# RAUPS_SingleLayer_Stepper.net
KiCad netlist of a schematic drawn in EAGLE
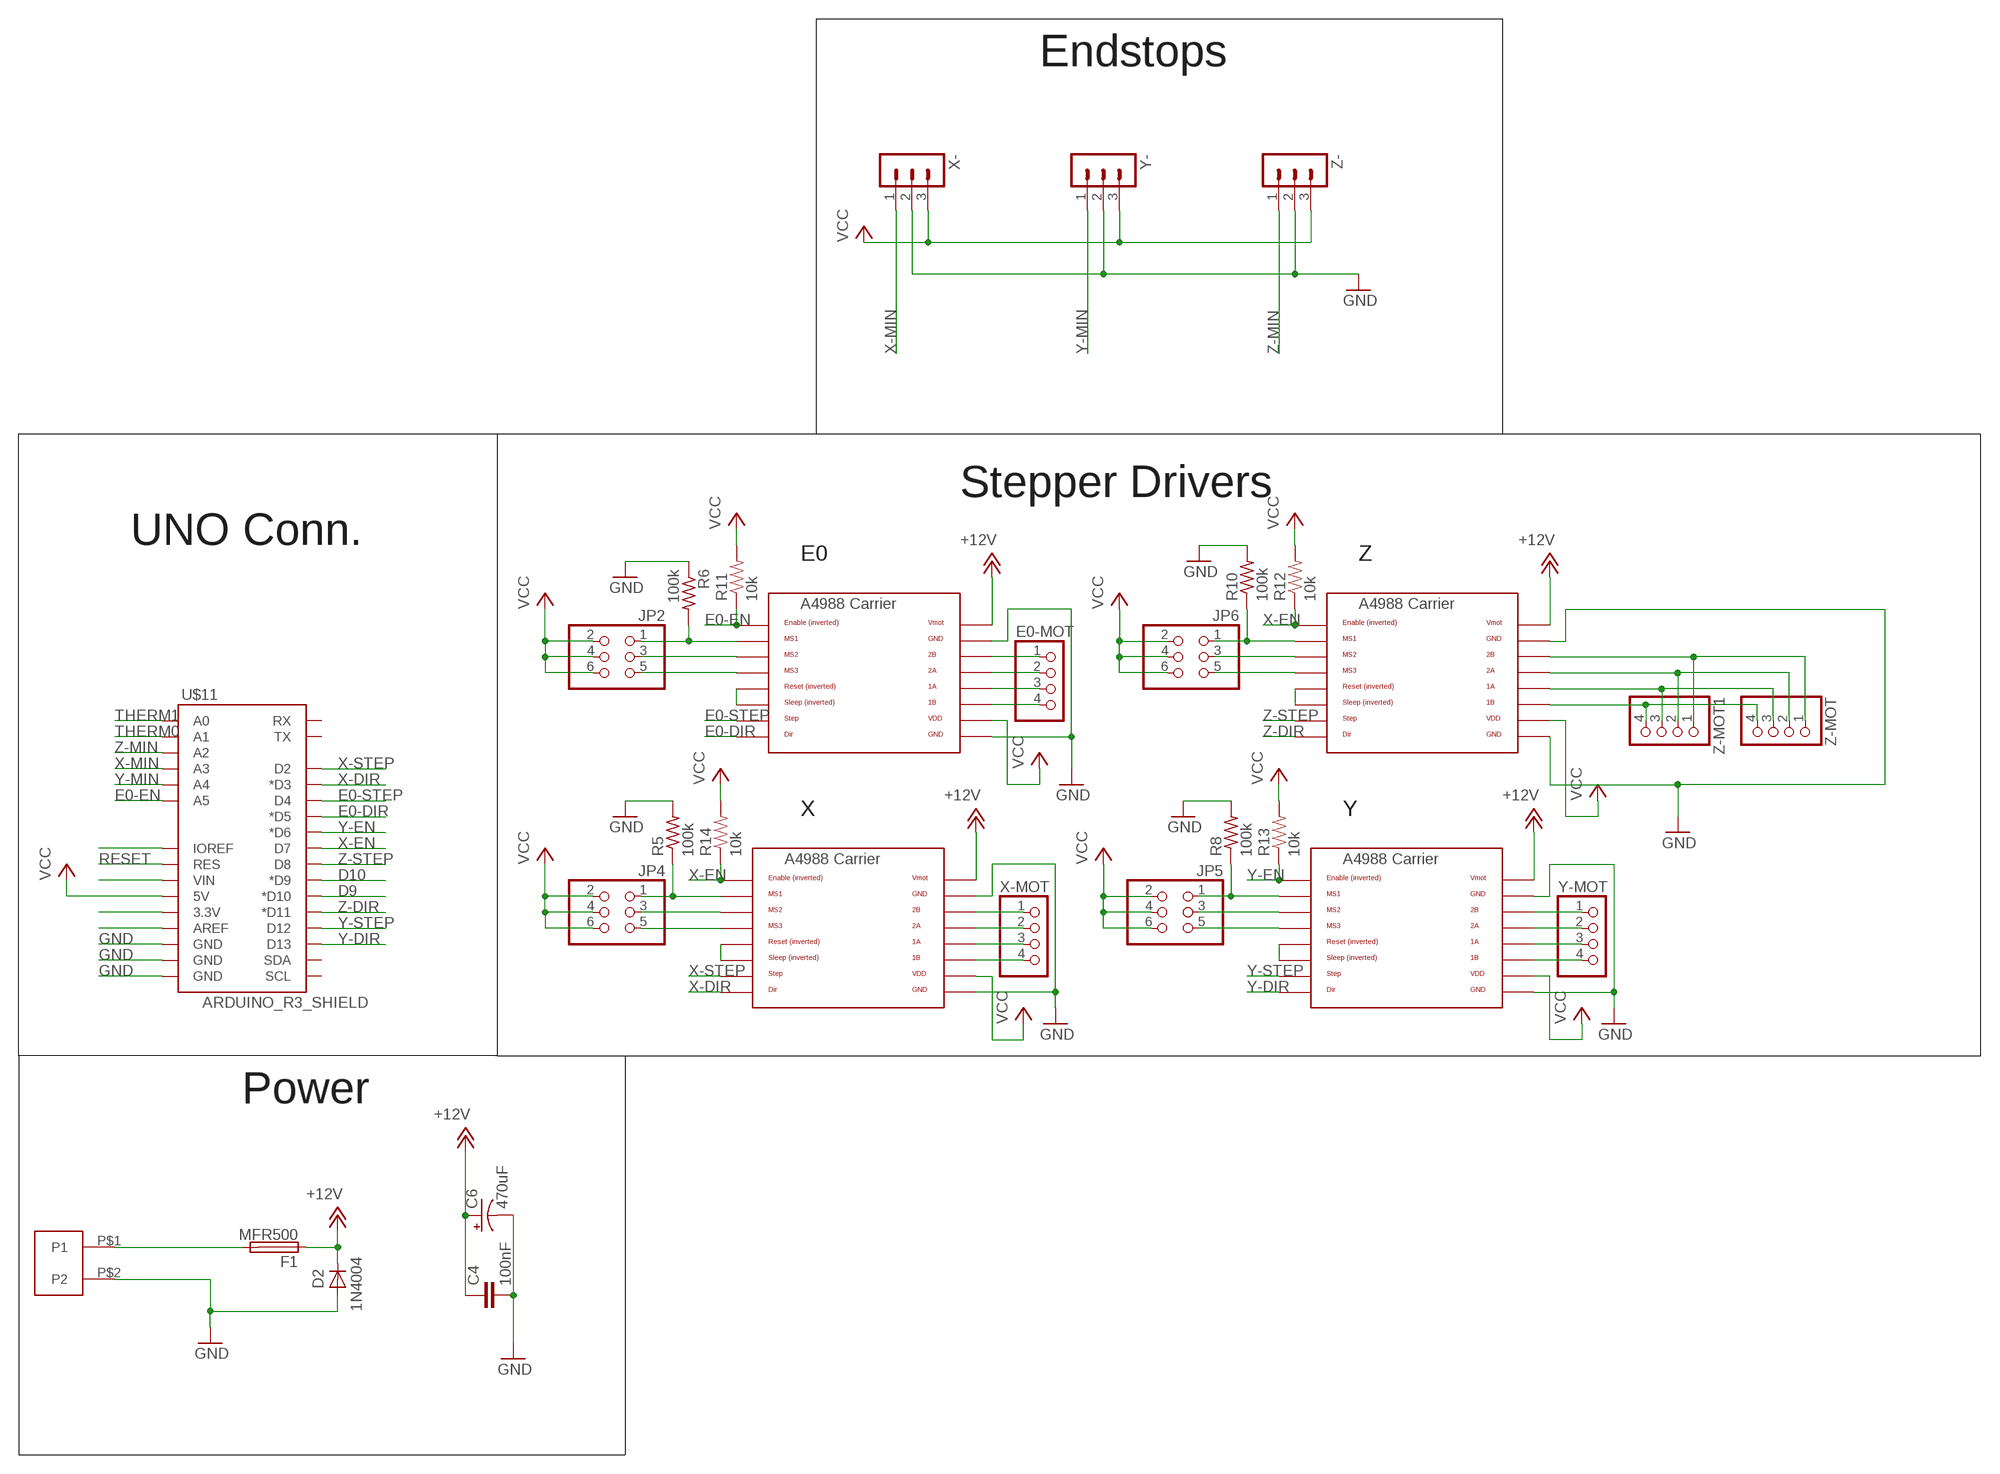
[diagram p0: schematic, sheet 1]

(export (version "E")
  (design (tool "Eeschema 10.0.6"))
  (components
    (comp (ref "C4")
      (value "100nF")
      (footprint "eagle-import:C2.5-3")
      (libsource (lib "eagle-import") (part "C2,5-3"))
    )
    (comp (ref "C6")
      (value "470uF")
      (footprint "eagle-import:E3,5-8")
      (libsource (lib "eagle-import") (part "CPOL-USE3.5-8"))
    )
    (comp (ref "D2")
      (value "1N4004")
      (footprint "eagle-import:DO41-10")
      (libsource (lib "eagle-import") (part "1N4004"))
    )
    (comp (ref "E0-MOT")
      (value "PINHD-1X4")
      (footprint "eagle-import:1X04")
      (libsource (lib "eagle-import") (part "PINHD-1X4"))
    )
    (comp (ref "F1")
      (value "MFR500")
      (footprint "eagle-import:MFR500")
      (libsource (lib "eagle-import") (part "PTCFUSE"))
    )
    (comp (ref "JP2")
      (value "PINHD-2X3")
      (footprint "eagle-import:2X03")
      (libsource (lib "eagle-import") (part "PINHD-2X3"))
    )
    (comp (ref "JP4")
      (value "PINHD-2X3")
      (footprint "eagle-import:2X03")
      (libsource (lib "eagle-import") (part "PINHD-2X3"))
    )
    (comp (ref "JP5")
      (value "PINHD-2X3")
      (footprint "eagle-import:2X03")
      (libsource (lib "eagle-import") (part "PINHD-2X3"))
    )
    (comp (ref "JP6")
      (value "PINHD-2X3")
      (footprint "eagle-import:2X03")
      (libsource (lib "eagle-import") (part "PINHD-2X3"))
    )
    (comp (ref "R5")
      (value "100k")
      (footprint "eagle-import:0207_7")
      (libsource (lib "eagle-import") (part "R-US_0207/7"))
    )
    (comp (ref "R6")
      (value "100k")
      (footprint "eagle-import:0207_7")
      (libsource (lib "eagle-import") (part "R-US_0207/7"))
    )
    (comp (ref "R8")
      (value "100k")
      (footprint "eagle-import:0207_7")
      (libsource (lib "eagle-import") (part "R-US_0207/7"))
    )
    (comp (ref "R10")
      (value "100k")
      (footprint "eagle-import:0207_7")
      (libsource (lib "eagle-import") (part "R-US_0207/7"))
    )
    (comp (ref "R11")
      (value "10k")
      (footprint "eagle-import:AXIAL-0.3")
      (libsource (lib "eagle-import") (part "10KOHM-1/4W-1%(PTH)HORIZ"))
    )
    (comp (ref "R12")
      (value "10k")
      (footprint "eagle-import:AXIAL-0.3")
      (libsource (lib "eagle-import") (part "10KOHM-1/4W-1%(PTH)HORIZ"))
    )
    (comp (ref "R13")
      (value "10k")
      (footprint "eagle-import:AXIAL-0.3")
      (libsource (lib "eagle-import") (part "10KOHM-1/4W-1%(PTH)HORIZ"))
    )
    (comp (ref "R14")
      (value "10k")
      (footprint "eagle-import:AXIAL-0.3")
      (libsource (lib "eagle-import") (part "10KOHM-1/4W-1%(PTH)HORIZ"))
    )
    (comp (ref "U$1")
      (value "2PIN_SOCKET")
      (footprint "eagle-import:CONN-2PIN")
      (libsource (lib "eagle-import") (part "2PIN_SOCKET"))
    )
    (comp (ref "U$4")
      (value "A4988BREAKOUT")
      (footprint "eagle-import:A4988BREAKOUT")
      (libsource (lib "eagle-import") (part "A4988BREAKOUT"))
    )
    (comp (ref "U$6")
      (value "A4988BREAKOUT")
      (footprint "eagle-import:A4988BREAKOUT")
      (libsource (lib "eagle-import") (part "A4988BREAKOUT"))
    )
    (comp (ref "U$7")
      (value "A4988BREAKOUT")
      (footprint "eagle-import:A4988BREAKOUT")
      (libsource (lib "eagle-import") (part "A4988BREAKOUT"))
    )
    (comp (ref "U$8")
      (value "A4988BREAKOUT")
      (footprint "eagle-import:A4988BREAKOUT")
      (libsource (lib "eagle-import") (part "A4988BREAKOUT"))
    )
    (comp (ref "U$11")
      (value "ARDUINO_R3_SHIELD")
      (footprint "eagle-import:UNO_R3_SHIELD")
      (libsource (lib "eagle-import") (part "ARDUINO_R3_SHIELD"))
    )
    (comp (ref "X-")
      (value "3PIN-HEADER")
      (footprint "eagle-import:3PIN-HEADER")
      (libsource (lib "eagle-import") (part "3PIN-HEADER"))
    )
    (comp (ref "X-MOT")
      (value "PINHD-1X4")
      (footprint "eagle-import:1X04")
      (libsource (lib "eagle-import") (part "PINHD-1X4"))
    )
    (comp (ref "Y-")
      (value "3PIN-HEADER")
      (footprint "eagle-import:3PIN-HEADER")
      (libsource (lib "eagle-import") (part "3PIN-HEADER"))
    )
    (comp (ref "Y-MOT")
      (value "PINHD-1X4")
      (footprint "eagle-import:1X04")
      (libsource (lib "eagle-import") (part "PINHD-1X4"))
    )
    (comp (ref "Z-")
      (value "3PIN-HEADER")
      (footprint "eagle-import:3PIN-HEADER")
      (libsource (lib "eagle-import") (part "3PIN-HEADER"))
    )
    (comp (ref "Z-MOT")
      (value "PINHD-1X4")
      (footprint "eagle-import:1X04")
      (libsource (lib "eagle-import") (part "PINHD-1X4"))
    )
    (comp (ref "Z-MOT1")
      (value "PINHD-1X4")
      (footprint "eagle-import:1X04")
      (libsource (lib "eagle-import") (part "PINHD-1X4"))
    )
  )
  (nets
    (net (code "1") (name "+12V") (class "Default")
      (node (ref "C4") (pin "1") (pinfunction "1_1") (pintype "passive"))
      (node (ref "C6") (pin "+") (pinfunction "+_+") (pintype "passive"))
      (node (ref "D2") (pin "C") (pinfunction "C_C") (pintype "passive"))
      (node (ref "F1") (pin "1") (pinfunction "1_1") (pintype "passive"))
      (node (ref "U$4") (pin "VMOT") (pinfunction "VMOT_VMOT") (pintype "power_in"))
      (node (ref "U$6") (pin "VMOT") (pinfunction "VMOT_VMOT") (pintype "power_in"))
      (node (ref "U$7") (pin "VMOT") (pinfunction "VMOT_VMOT") (pintype "power_in"))
      (node (ref "U$8") (pin "VMOT") (pinfunction "VMOT_VMOT") (pintype "power_in"))
    )
    (net (code "2") (name "/D9") (class "Default")
      (node (ref "U$11") (pin "D10") (pinfunction "*D10_D10") (pintype "bidirectional"))
    )
    (net (code "3") (name "/D10") (class "Default")
      (node (ref "U$11") (pin "D9") (pinfunction "*D9_D9") (pintype "bidirectional"))
    )
    (net (code "4") (name "/E0-DIR") (class "Default")
      (node (ref "U$11") (pin "D5") (pinfunction "*D5_D5") (pintype "bidirectional"))
      (node (ref "U$4") (pin "DIR") (pinfunction "DIR_DIR") (pintype "input"))
    )
    (net (code "5") (name "/E0-EN") (class "Default")
      (node (ref "R11") (pin "P$1") (pinfunction "1_P$1") (pintype "passive"))
      (node (ref "U$11") (pin "A5") (pinfunction "A5_A5") (pintype "bidirectional"))
      (node (ref "U$4") (pin "EN") (pinfunction "EN_EN") (pintype "input"))
    )
    (net (code "6") (name "/E0-STEP") (class "Default")
      (node (ref "U$11") (pin "D4") (pinfunction "D4_D4") (pintype "bidirectional"))
      (node (ref "U$4") (pin "STEP") (pinfunction "STEP_STEP") (pintype "input"))
    )
    (net (code "7") (name "/RESET") (class "Default")
      (node (ref "U$11") (pin "RES") (pinfunction "RES_RES") (pintype "bidirectional"))
    )
    (net (code "8") (name "/THERM0") (class "Default")
      (node (ref "U$11") (pin "A1") (pinfunction "A1_A1") (pintype "bidirectional"))
    )
    (net (code "9") (name "/THERM1") (class "Default")
      (node (ref "U$11") (pin "A0") (pinfunction "A0_A0") (pintype "bidirectional"))
    )
    (net (code "10") (name "/X-DIR") (class "Default")
      (node (ref "U$11") (pin "D3") (pinfunction "*D3_D3") (pintype "bidirectional"))
      (node (ref "U$6") (pin "DIR") (pinfunction "DIR_DIR") (pintype "input"))
    )
    (net (code "11") (name "/X-EN") (class "Default")
      (node (ref "R12") (pin "P$1") (pinfunction "1_P$1") (pintype "passive"))
      (node (ref "R14") (pin "P$1") (pinfunction "1_P$1") (pintype "passive"))
      (node (ref "U$11") (pin "D7") (pinfunction "D7_D7") (pintype "bidirectional"))
      (node (ref "U$6") (pin "EN") (pinfunction "EN_EN") (pintype "input"))
      (node (ref "U$8") (pin "EN") (pinfunction "EN_EN") (pintype "input"))
    )
    (net (code "12") (name "/X-MIN") (class "Default")
      (node (ref "U$11") (pin "A3") (pinfunction "A3_A3") (pintype "bidirectional"))
      (node (ref "X-") (pin "1") (pinfunction "1_1") (pintype "passive"))
    )
    (net (code "13") (name "/X-STEP") (class "Default")
      (node (ref "U$11") (pin "D2") (pinfunction "D2_D2") (pintype "bidirectional"))
      (node (ref "U$6") (pin "STEP") (pinfunction "STEP_STEP") (pintype "input"))
    )
    (net (code "14") (name "/Y-DIR") (class "Default")
      (node (ref "U$11") (pin "D13") (pinfunction "D13_D13") (pintype "bidirectional"))
      (node (ref "U$7") (pin "DIR") (pinfunction "DIR_DIR") (pintype "input"))
    )
    (net (code "15") (name "/Y-EN") (class "Default")
      (node (ref "R13") (pin "P$1") (pinfunction "1_P$1") (pintype "passive"))
      (node (ref "U$11") (pin "D6") (pinfunction "*D6_D6") (pintype "bidirectional"))
      (node (ref "U$7") (pin "EN") (pinfunction "EN_EN") (pintype "input"))
    )
    (net (code "16") (name "/Y-MIN") (class "Default")
      (node (ref "U$11") (pin "A4") (pinfunction "A4_A4") (pintype "bidirectional"))
      (node (ref "Y-") (pin "1") (pinfunction "1_1") (pintype "passive"))
    )
    (net (code "17") (name "/Y-STEP") (class "Default")
      (node (ref "U$11") (pin "D12") (pinfunction "D12_D12") (pintype "bidirectional"))
      (node (ref "U$7") (pin "STEP") (pinfunction "STEP_STEP") (pintype "input"))
    )
    (net (code "18") (name "/Z-DIR") (class "Default")
      (node (ref "U$11") (pin "D11") (pinfunction "*D11_D11") (pintype "bidirectional"))
      (node (ref "U$8") (pin "DIR") (pinfunction "DIR_DIR") (pintype "input"))
    )
    (net (code "19") (name "/Z-MIN") (class "Default")
      (node (ref "U$11") (pin "A2") (pinfunction "A2_A2") (pintype "bidirectional"))
      (node (ref "Z-") (pin "1") (pinfunction "1_1") (pintype "passive"))
    )
    (net (code "20") (name "/Z-STEP") (class "Default")
      (node (ref "U$11") (pin "D8") (pinfunction "D8_D8") (pintype "bidirectional"))
      (node (ref "U$8") (pin "STEP") (pinfunction "STEP_STEP") (pintype "input"))
    )
    (net (code "21") (name "GND") (class "Default")
      (node (ref "C4") (pin "2") (pinfunction "2_2") (pintype "passive"))
      (node (ref "C6") (pin "-") (pinfunction "-_-") (pintype "passive"))
      (node (ref "D2") (pin "A") (pinfunction "A_A") (pintype "passive"))
      (node (ref "R10") (pin "2") (pinfunction "2_2") (pintype "passive"))
      (node (ref "R5") (pin "2") (pinfunction "2_2") (pintype "passive"))
      (node (ref "R6") (pin "1") (pinfunction "1_1") (pintype "passive"))
      (node (ref "R8") (pin "2") (pinfunction "2_2") (pintype "passive"))
      (node (ref "U$1") (pin "P$2") (pinfunction "P2_P$2") (pintype "bidirectional"))
      (node (ref "U$11") (pin "GND@0") (pinfunction "GND_GND@0") (pintype "bidirectional"))
      (node (ref "U$11") (pin "GND@1") (pinfunction "GND_GND@1") (pintype "bidirectional"))
      (node (ref "U$11") (pin "GND@2") (pinfunction "GND_GND@2") (pintype "bidirectional"))
      (node (ref "U$4") (pin "GND") (pinfunction "GND_GND") (pintype "power_in"))
      (node (ref "U$4") (pin "GND@0") (pinfunction "GND_GND@0") (pintype "power_in"))
      (node (ref "U$6") (pin "GND") (pinfunction "GND_GND") (pintype "power_in"))
      (node (ref "U$6") (pin "GND@0") (pinfunction "GND_GND@0") (pintype "power_in"))
      (node (ref "U$7") (pin "GND") (pinfunction "GND_GND") (pintype "power_in"))
      (node (ref "U$7") (pin "GND@0") (pinfunction "GND_GND@0") (pintype "power_in"))
      (node (ref "U$8") (pin "GND") (pinfunction "GND_GND") (pintype "power_in"))
      (node (ref "U$8") (pin "GND@0") (pinfunction "GND_GND@0") (pintype "power_in"))
      (node (ref "X-") (pin "2") (pinfunction "2_2") (pintype "passive"))
      (node (ref "Y-") (pin "2") (pinfunction "2_2") (pintype "passive"))
      (node (ref "Z-") (pin "2") (pinfunction "2_2") (pintype "passive"))
    )
    (net (code "22") (name "Net-(E0-MOT-Pad1)") (class "Default")
      (node (ref "E0-MOT") (pin "1") (pinfunction "1_1") (pintype "passive"))
      (node (ref "U$4") (pin "2B") (pinfunction "2B_2B") (pintype "output"))
    )
    (net (code "23") (name "Net-(E0-MOT-Pad2)") (class "Default")
      (node (ref "E0-MOT") (pin "2") (pinfunction "2_2") (pintype "passive"))
      (node (ref "U$4") (pin "2A") (pinfunction "2A_2A") (pintype "output"))
    )
    (net (code "24") (name "Net-(E0-MOT-Pad3)") (class "Default")
      (node (ref "E0-MOT") (pin "3") (pinfunction "3_3") (pintype "passive"))
      (node (ref "U$4") (pin "1A") (pinfunction "1A_1A") (pintype "output"))
    )
    (net (code "25") (name "Net-(E0-MOT-Pad4)") (class "Default")
      (node (ref "E0-MOT") (pin "4") (pinfunction "4_4") (pintype "passive"))
      (node (ref "U$4") (pin "1B") (pinfunction "1B_1B") (pintype "output"))
    )
    (net (code "26") (name "Net-(JP2-Pad1)") (class "Default")
      (node (ref "JP2") (pin "1") (pinfunction "1_1") (pintype "passive"))
      (node (ref "R6") (pin "2") (pinfunction "2_2") (pintype "passive"))
      (node (ref "U$4") (pin "MS1") (pinfunction "MS1_MS1") (pintype "input"))
    )
    (net (code "27") (name "Net-(JP2-Pad3)") (class "Default")
      (node (ref "JP2") (pin "3") (pinfunction "3_3") (pintype "passive"))
      (node (ref "U$4") (pin "MS2") (pinfunction "MS2_MS2") (pintype "input"))
    )
    (net (code "28") (name "Net-(JP2-Pad5)") (class "Default")
      (node (ref "JP2") (pin "5") (pinfunction "5_5") (pintype "passive"))
      (node (ref "U$4") (pin "MS3") (pinfunction "MS3_MS3") (pintype "input"))
    )
    (net (code "29") (name "Net-(JP4-Pad1)") (class "Default")
      (node (ref "JP4") (pin "1") (pinfunction "1_1") (pintype "passive"))
      (node (ref "R5") (pin "1") (pinfunction "1_1") (pintype "passive"))
      (node (ref "U$6") (pin "MS1") (pinfunction "MS1_MS1") (pintype "input"))
    )
    (net (code "30") (name "Net-(JP4-Pad3)") (class "Default")
      (node (ref "JP4") (pin "3") (pinfunction "3_3") (pintype "passive"))
      (node (ref "U$6") (pin "MS2") (pinfunction "MS2_MS2") (pintype "input"))
    )
    (net (code "31") (name "Net-(JP4-Pad5)") (class "Default")
      (node (ref "JP4") (pin "5") (pinfunction "5_5") (pintype "passive"))
      (node (ref "U$6") (pin "MS3") (pinfunction "MS3_MS3") (pintype "input"))
    )
    (net (code "32") (name "Net-(JP5-Pad1)") (class "Default")
      (node (ref "JP5") (pin "1") (pinfunction "1_1") (pintype "passive"))
      (node (ref "R8") (pin "1") (pinfunction "1_1") (pintype "passive"))
      (node (ref "U$7") (pin "MS1") (pinfunction "MS1_MS1") (pintype "input"))
    )
    (net (code "33") (name "Net-(JP5-Pad3)") (class "Default")
      (node (ref "JP5") (pin "3") (pinfunction "3_3") (pintype "passive"))
      (node (ref "U$7") (pin "MS2") (pinfunction "MS2_MS2") (pintype "input"))
    )
    (net (code "34") (name "Net-(JP5-Pad5)") (class "Default")
      (node (ref "JP5") (pin "5") (pinfunction "5_5") (pintype "passive"))
      (node (ref "U$7") (pin "MS3") (pinfunction "MS3_MS3") (pintype "input"))
    )
    (net (code "35") (name "Net-(JP6-Pad1)") (class "Default")
      (node (ref "JP6") (pin "1") (pinfunction "1_1") (pintype "passive"))
      (node (ref "R10") (pin "1") (pinfunction "1_1") (pintype "passive"))
      (node (ref "U$8") (pin "MS1") (pinfunction "MS1_MS1") (pintype "input"))
    )
    (net (code "36") (name "Net-(JP6-Pad3)") (class "Default")
      (node (ref "JP6") (pin "3") (pinfunction "3_3") (pintype "passive"))
      (node (ref "U$8") (pin "MS2") (pinfunction "MS2_MS2") (pintype "input"))
    )
    (net (code "37") (name "Net-(JP6-Pad5)") (class "Default")
      (node (ref "JP6") (pin "5") (pinfunction "5_5") (pintype "passive"))
      (node (ref "U$8") (pin "MS3") (pinfunction "MS3_MS3") (pintype "input"))
    )
    (net (code "38") (name "Net-(U$1-P1)") (class "Default")
      (node (ref "F1") (pin "2") (pinfunction "2_2") (pintype "passive"))
      (node (ref "U$1") (pin "P$1") (pinfunction "P1_P$1") (pintype "bidirectional"))
    )
    (net (code "39") (name "Net-(U$4-SLEEP)") (class "Default")
      (node (ref "U$4") (pin "RST") (pinfunction "RST_RST") (pintype "input"))
      (node (ref "U$4") (pin "SLP") (pinfunction "SLEEP_SLP") (pintype "input"))
    )
    (net (code "40") (name "Net-(U$6-Pad1A)") (class "Default")
      (node (ref "U$6") (pin "1A") (pinfunction "1A_1A") (pintype "output"))
      (node (ref "X-MOT") (pin "3") (pinfunction "3_3") (pintype "passive"))
    )
    (net (code "41") (name "Net-(U$6-Pad1B)") (class "Default")
      (node (ref "U$6") (pin "1B") (pinfunction "1B_1B") (pintype "output"))
      (node (ref "X-MOT") (pin "4") (pinfunction "4_4") (pintype "passive"))
    )
    (net (code "42") (name "Net-(U$6-Pad2A)") (class "Default")
      (node (ref "U$6") (pin "2A") (pinfunction "2A_2A") (pintype "output"))
      (node (ref "X-MOT") (pin "2") (pinfunction "2_2") (pintype "passive"))
    )
    (net (code "43") (name "Net-(U$6-Pad2B)") (class "Default")
      (node (ref "U$6") (pin "2B") (pinfunction "2B_2B") (pintype "output"))
      (node (ref "X-MOT") (pin "1") (pinfunction "1_1") (pintype "passive"))
    )
    (net (code "44") (name "Net-(U$6-SLEEP)") (class "Default")
      (node (ref "U$6") (pin "RST") (pinfunction "RST_RST") (pintype "input"))
      (node (ref "U$6") (pin "SLP") (pinfunction "SLEEP_SLP") (pintype "input"))
    )
    (net (code "45") (name "Net-(U$7-Pad1A)") (class "Default")
      (node (ref "U$7") (pin "1A") (pinfunction "1A_1A") (pintype "output"))
      (node (ref "Y-MOT") (pin "3") (pinfunction "3_3") (pintype "passive"))
    )
    (net (code "46") (name "Net-(U$7-Pad1B)") (class "Default")
      (node (ref "U$7") (pin "1B") (pinfunction "1B_1B") (pintype "output"))
      (node (ref "Y-MOT") (pin "4") (pinfunction "4_4") (pintype "passive"))
    )
    (net (code "47") (name "Net-(U$7-Pad2A)") (class "Default")
      (node (ref "U$7") (pin "2A") (pinfunction "2A_2A") (pintype "output"))
      (node (ref "Y-MOT") (pin "2") (pinfunction "2_2") (pintype "passive"))
    )
    (net (code "48") (name "Net-(U$7-Pad2B)") (class "Default")
      (node (ref "U$7") (pin "2B") (pinfunction "2B_2B") (pintype "output"))
      (node (ref "Y-MOT") (pin "1") (pinfunction "1_1") (pintype "passive"))
    )
    (net (code "49") (name "Net-(U$7-SLEEP)") (class "Default")
      (node (ref "U$7") (pin "RST") (pinfunction "RST_RST") (pintype "input"))
      (node (ref "U$7") (pin "SLP") (pinfunction "SLEEP_SLP") (pintype "input"))
    )
    (net (code "50") (name "Net-(U$8-Pad1A)") (class "Default")
      (node (ref "U$8") (pin "1A") (pinfunction "1A_1A") (pintype "output"))
      (node (ref "Z-MOT") (pin "3") (pinfunction "3_3") (pintype "passive"))
      (node (ref "Z-MOT1") (pin "3") (pinfunction "3_3") (pintype "passive"))
    )
    (net (code "51") (name "Net-(U$8-Pad1B)") (class "Default")
      (node (ref "U$8") (pin "1B") (pinfunction "1B_1B") (pintype "output"))
      (node (ref "Z-MOT") (pin "4") (pinfunction "4_4") (pintype "passive"))
      (node (ref "Z-MOT1") (pin "4") (pinfunction "4_4") (pintype "passive"))
    )
    (net (code "52") (name "Net-(U$8-Pad2A)") (class "Default")
      (node (ref "U$8") (pin "2A") (pinfunction "2A_2A") (pintype "output"))
      (node (ref "Z-MOT") (pin "2") (pinfunction "2_2") (pintype "passive"))
      (node (ref "Z-MOT1") (pin "2") (pinfunction "2_2") (pintype "passive"))
    )
    (net (code "53") (name "Net-(U$8-Pad2B)") (class "Default")
      (node (ref "U$8") (pin "2B") (pinfunction "2B_2B") (pintype "output"))
      (node (ref "Z-MOT") (pin "1") (pinfunction "1_1") (pintype "passive"))
      (node (ref "Z-MOT1") (pin "1") (pinfunction "1_1") (pintype "passive"))
    )
    (net (code "54") (name "Net-(U$8-SLEEP)") (class "Default")
      (node (ref "U$8") (pin "RST") (pinfunction "RST_RST") (pintype "input"))
      (node (ref "U$8") (pin "SLP") (pinfunction "SLEEP_SLP") (pintype "input"))
    )
    (net (code "55") (name "VCC") (class "Default")
      (node (ref "JP2") (pin "2") (pinfunction "2_2") (pintype "passive"))
      (node (ref "JP2") (pin "4") (pinfunction "4_4") (pintype "passive"))
      (node (ref "JP2") (pin "6") (pinfunction "6_6") (pintype "passive"))
      (node (ref "JP4") (pin "2") (pinfunction "2_2") (pintype "passive"))
      (node (ref "JP4") (pin "4") (pinfunction "4_4") (pintype "passive"))
      (node (ref "JP4") (pin "6") (pinfunction "6_6") (pintype "passive"))
      (node (ref "JP5") (pin "2") (pinfunction "2_2") (pintype "passive"))
      (node (ref "JP5") (pin "4") (pinfunction "4_4") (pintype "passive"))
      (node (ref "JP5") (pin "6") (pinfunction "6_6") (pintype "passive"))
      (node (ref "JP6") (pin "2") (pinfunction "2_2") (pintype "passive"))
      (node (ref "JP6") (pin "4") (pinfunction "4_4") (pintype "passive"))
      (node (ref "JP6") (pin "6") (pinfunction "6_6") (pintype "passive"))
      (node (ref "R11") (pin "P$2") (pinfunction "2_P$2") (pintype "passive"))
      (node (ref "R12") (pin "P$2") (pinfunction "2_P$2") (pintype "passive"))
      (node (ref "R13") (pin "P$2") (pinfunction "2_P$2") (pintype "passive"))
      (node (ref "R14") (pin "P$2") (pinfunction "2_P$2") (pintype "passive"))
      (node (ref "U$11") (pin "5V") (pinfunction "5V_5V") (pintype "bidirectional"))
      (node (ref "U$4") (pin "VDD") (pinfunction "VDD_VDD") (pintype "power_in"))
      (node (ref "U$6") (pin "VDD") (pinfunction "VDD_VDD") (pintype "power_in"))
      (node (ref "U$7") (pin "VDD") (pinfunction "VDD_VDD") (pintype "power_in"))
      (node (ref "U$8") (pin "VDD") (pinfunction "VDD_VDD") (pintype "power_in"))
      (node (ref "X-") (pin "3") (pinfunction "3_3") (pintype "passive"))
      (node (ref "Y-") (pin "3") (pinfunction "3_3") (pintype "passive"))
      (node (ref "Z-") (pin "3") (pinfunction "3_3") (pintype "passive"))
    )
    (net (code "56") (name "unconnected-(U$11-Pad3.3V)") (class "Default")
      (node (ref "U$11") (pin "3.3V") (pinfunction "3.3V_3.3V") (pintype "bidirectional"))
    )
    (net (code "57") (name "unconnected-(U$11-PadAREF)") (class "Default")
      (node (ref "U$11") (pin "AREF") (pinfunction "AREF_AREF") (pintype "bidirectional"))
    )
    (net (code "58") (name "unconnected-(U$11-PadIOREF)") (class "Default")
      (node (ref "U$11") (pin "IOREF") (pinfunction "IOREF_IOREF") (pintype "bidirectional"))
    )
    (net (code "59") (name "unconnected-(U$11-PadRX)") (class "Default")
      (node (ref "U$11") (pin "RX") (pinfunction "RX_RX") (pintype "bidirectional"))
    )
    (net (code "60") (name "unconnected-(U$11-PadSCL)") (class "Default")
      (node (ref "U$11") (pin "SCL") (pinfunction "SCL_SCL") (pintype "bidirectional"))
    )
    (net (code "61") (name "unconnected-(U$11-PadSDA)") (class "Default")
      (node (ref "U$11") (pin "SDA") (pinfunction "SDA_SDA") (pintype "bidirectional"))
    )
    (net (code "62") (name "unconnected-(U$11-PadTX)") (class "Default")
      (node (ref "U$11") (pin "TX") (pinfunction "TX_TX") (pintype "bidirectional"))
    )
    (net (code "63") (name "unconnected-(U$11-PadVIN)") (class "Default")
      (node (ref "U$11") (pin "VIN") (pinfunction "VIN_VIN") (pintype "bidirectional"))
    )
  )
)
